# machdongho.net
KiCad netlist of a schematic drawn in Altium Designer
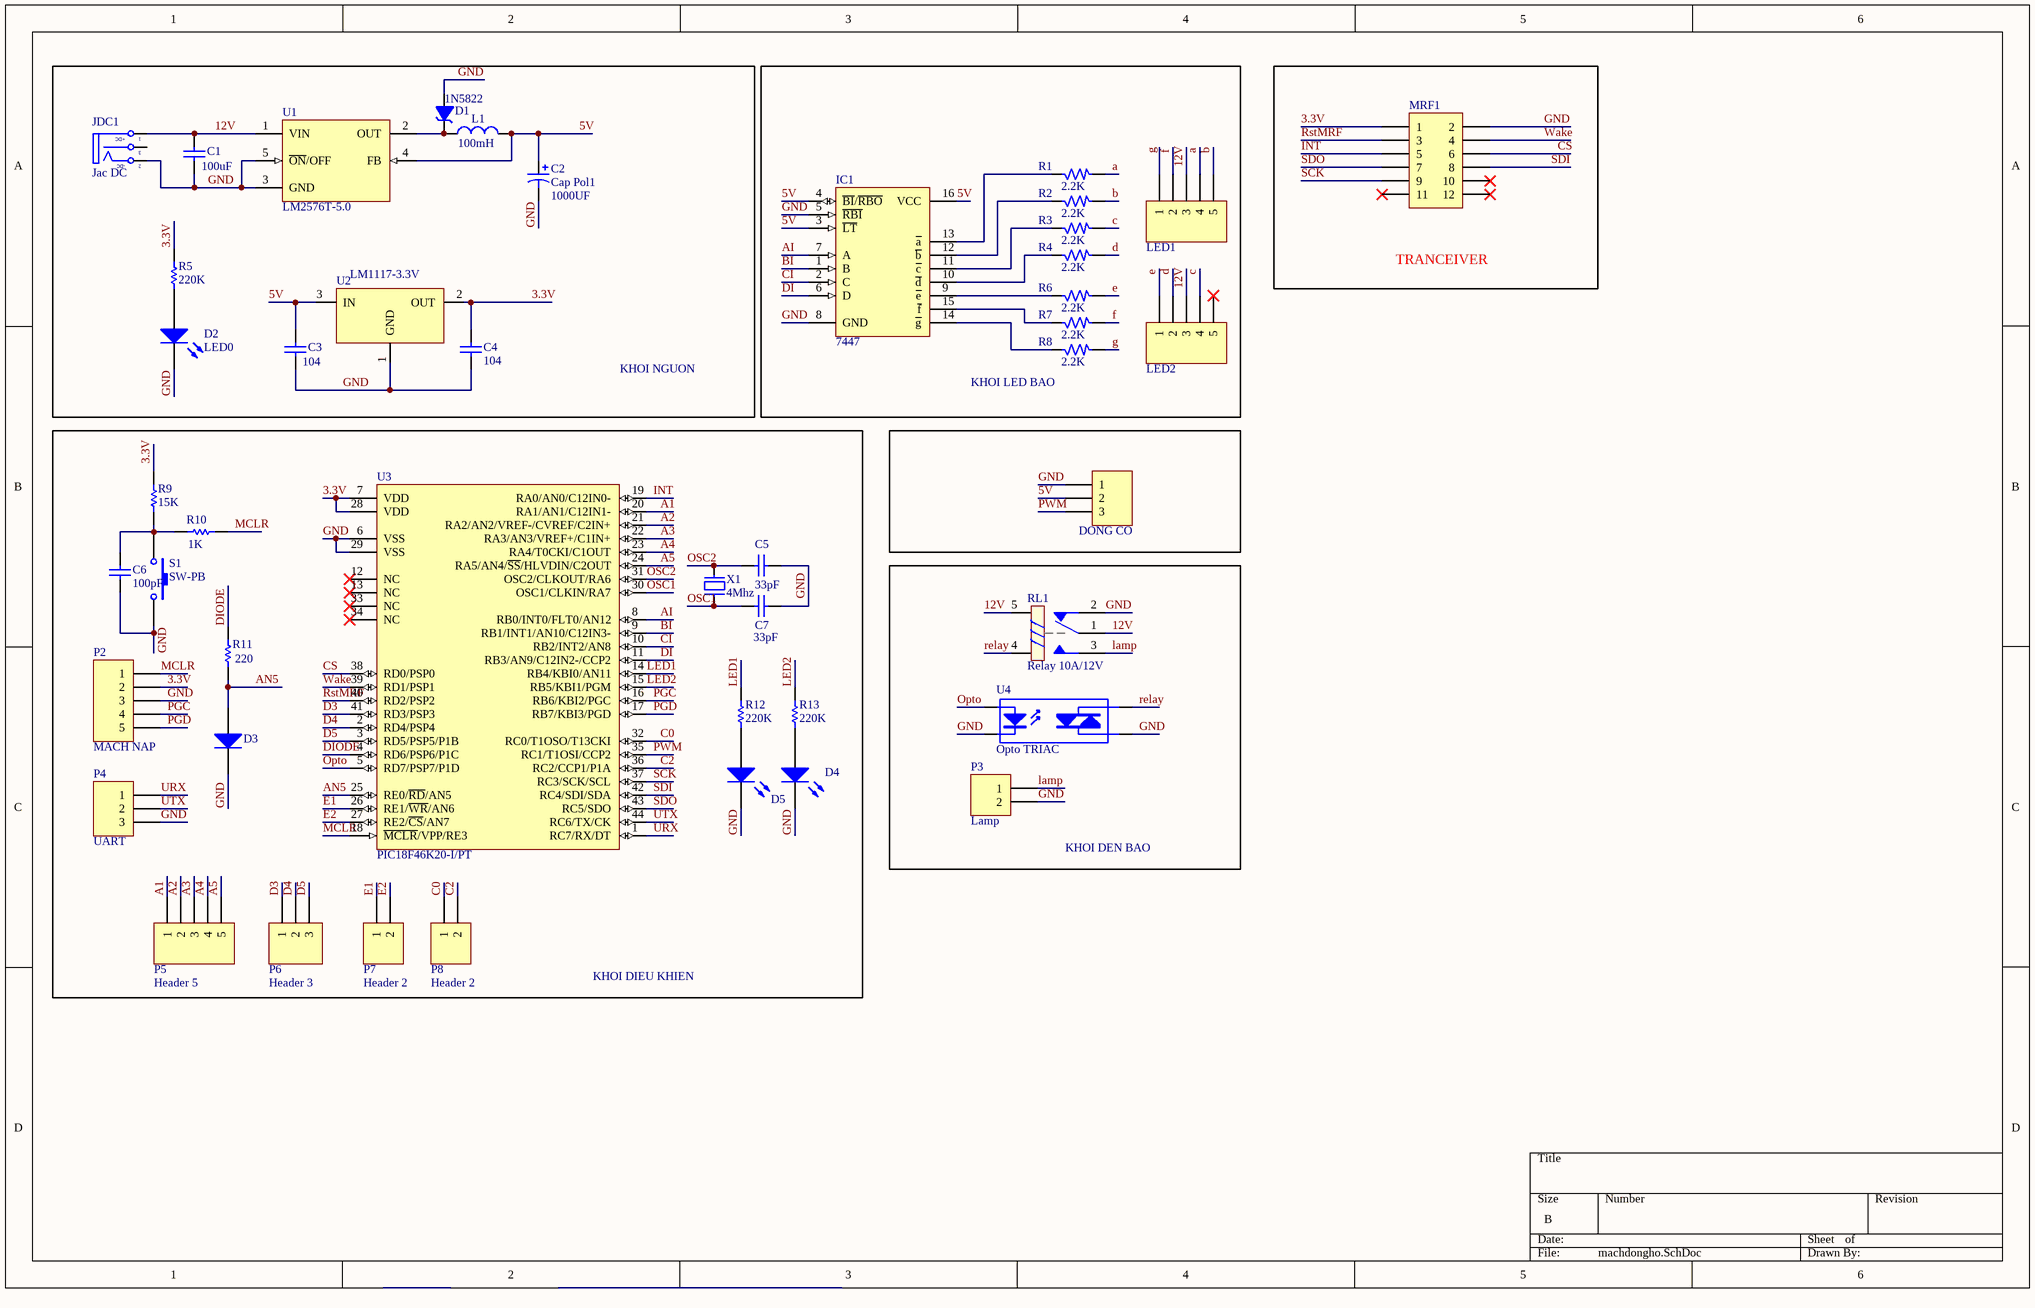
[diagram p0: machdongho.SchDoc]

(export (version "E")
  (design (tool "Eeschema 10.0.6"))
  (components
    (comp (ref "C1")
      (value "100uF")
      (footprint "SMD Capacistor 1206")
      (description "Capacitor")
      (fields (field (name "Comment") "Cap") (field (name "PUBLISHER") "Altium Limited"))
      (libsource (lib "Miscellaneous Devices") (part "Cap"))
    )
    (comp (ref "C2")
      (value "Cap Pol1")
      (footprint "SMD Capacistor 1206")
      (description "Polarized Capacitor (Radial)")
      (fields (field (name "ALTIUM_VALUE") "1000UF") (field (name "PUBLISHER") "Altium Limited"))
      (libsource (lib "Miscellaneous Devices") (part "Cap Pol1"))
    )
    (comp (ref "C3")
      (value "104")
      (footprint "SM-0805")
      (description "Capacitor")
      (fields (field (name "Comment") "Cap") (field (name "PUBLISHER") "Altium Limited"))
      (libsource (lib "Miscellaneous Devices") (part "Cap"))
    )
    (comp (ref "C4")
      (value "104")
      (footprint "SM-0805")
      (description "Capacitor")
      (fields (field (name "Comment") "Cap") (field (name "PUBLISHER") "Altium Limited"))
      (libsource (lib "Miscellaneous Devices") (part "Cap"))
    )
    (comp (ref "C5")
      (value "33pF")
      (footprint "SM-0805")
      (description "Capacitor")
      (fields (field (name "PUBLISHER") "Altium Limited"))
      (libsource (lib "Miscellaneous Devices") (part "Cap"))
    )
    (comp (ref "C6")
      (value "100pF")
      (footprint "SM-0805")
      (description "Capacitor")
      (fields (field (name "Comment") "Cap") (field (name "PUBLISHER") "Altium Limited"))
      (libsource (lib "Miscellaneous Devices") (part "Cap"))
    )
    (comp (ref "C7")
      (value "33pF")
      (footprint "SM-0805")
      (description "Capacitor")
      (fields (field (name "PUBLISHER") "Altium Limited"))
      (libsource (lib "Miscellaneous Devices") (part "Cap"))
    )
    (comp (ref "D1")
      (value "1N5822")
      (footprint "DZ0.5A")
      (description "Diode Zenner")
      (libsource (lib "syhaunguyen") (part "DZ"))
    )
    (comp (ref "D2")
      (value "LED0")
      (footprint "LED-5 GRe")
      (description "Typical INFRARED GaAs LED")
      (fields (field (name "PUBLISHER") "Altium Limited"))
      (libsource (lib "Miscellaneous Devices") (part "LED0"))
    )
    (comp (ref "D3")
      (value "Diode")
      (footprint "SMC")
      (description "Default Diode")
      (fields (field (name "PUBLISHER") "Altium Limited"))
      (libsource (lib "Miscellaneous Devices") (part "Diode"))
    )
    (comp (ref "D4")
      (value "~")
      (footprint "LED-5 GRe")
      (description "Typical INFRARED GaAs LED")
      (fields (field (name "PUBLISHER") "Altium Limited"))
      (libsource (lib "Miscellaneous Devices") (part "LED0"))
    )
    (comp (ref "D5")
      (value "~")
      (footprint "LED-5 GRe")
      (description "Typical INFRARED GaAs LED")
      (fields (field (name "PUBLISHER") "Altium Limited"))
      (libsource (lib "Miscellaneous Devices") (part "LED0"))
    )
    (comp (ref "IC1")
      (value "7447")
      (footprint "DIP16/W0.3")
      (description "VanDungEvn")
      (libsource (lib "syhaunguyen") (part "7447"))
    )
    (comp (ref "JDC1")
      (value "Jac DC")
      (footprint "DC-IN")
      (description "Jac DC input")
      (libsource (lib "syhaunguyen") (part "DCIN"))
    )
    (comp (ref "L1")
      (value "100mH")
      (footprint "L/0.4")
      (description "Inductor")
      (libsource (lib "syhaunguyen") (part "L1"))
    )
    (comp (ref "LED1")
      (value "Led7")
      (footprint "HDR1X5")
      (description "Header, 5-Pin")
      (fields (field (name "PUBLISHER") "Altium Limited"))
      (libsource (lib "Miscellaneous Connectors") (part "Header 5"))
    )
    (comp (ref "LED2")
      (value "Led7")
      (footprint "HDR1X5")
      (description "Header, 5-Pin")
      (fields (field (name "PUBLISHER") "Altium Limited"))
      (libsource (lib "Miscellaneous Connectors") (part "Header 5"))
    )
    (comp (ref "MRF1")
      (value "Header 6X2")
      (footprint "MRF24J40MB_board_mini")
      (description "Header, 6-Pin, Dual row")
      (fields (field (name "PUBLISHER") "Altium Limited"))
      (libsource (lib "Miscellaneous Connectors") (part "Header 6X2"))
    )
    (comp (ref "P1")
      (value "DONG CO")
      (footprint "HDR1X3")
      (description "Header, 3-Pin")
      (fields (field (name "PUBLISHER") "Altium Limited"))
      (libsource (lib "Miscellaneous Connectors") (part "Header 3"))
    )
    (comp (ref "P2")
      (value "MACH NAP")
      (footprint "HDR1X5")
      (description "Header, 5-Pin")
      (fields (field (name "PUBLISHER") "Altium Limited"))
      (libsource (lib "") (part "Header 5_1"))
    )
    (comp (ref "P3")
      (value "Lamp")
      (footprint "HDR1X2")
      (description "Header, 2-Pin")
      (fields (field (name "PUBLISHER") "Altium Limited"))
      (libsource (lib "") (part "Header 2_1"))
    )
    (comp (ref "P4")
      (value "UART")
      (footprint "HDR1X3")
      (description "Header, 3-Pin")
      (fields (field (name "PUBLISHER") "Altium Limited"))
      (libsource (lib "") (part "Header 3_2"))
    )
    (comp (ref "P5")
      (value "Header 5")
      (footprint "HDR1X5")
      (description "Header, 5-Pin")
      (fields (field (name "PUBLISHER") "Altium Limited"))
      (libsource (lib "Miscellaneous Connectors") (part "Header 5"))
    )
    (comp (ref "P6")
      (value "Header 3")
      (footprint "HDR1X3")
      (description "Header, 3-Pin")
      (fields (field (name "PUBLISHER") "Altium Limited"))
      (libsource (lib "") (part "Header 3_1"))
    )
    (comp (ref "P7")
      (value "Header 2")
      (footprint "HDR1X2")
      (description "Header, 2-Pin")
      (fields (field (name "PUBLISHER") "Altium Limited"))
      (libsource (lib "Miscellaneous Connectors") (part "Header 2"))
    )
    (comp (ref "P8")
      (value "Header 2")
      (footprint "HDR1X2")
      (description "Header, 2-Pin")
      (fields (field (name "PUBLISHER") "Altium Limited"))
      (libsource (lib "Miscellaneous Connectors") (part "Header 2"))
    )
    (comp (ref "R1")
      (value "2.2K")
      (footprint "SM-0805")
      (description "Resistor 1/4W")
      (libsource (lib "syhaunguyen") (part "R"))
    )
    (comp (ref "R2")
      (value "2.2K")
      (footprint "SM-0805")
      (description "Resistor 1/4W")
      (libsource (lib "syhaunguyen") (part "R"))
    )
    (comp (ref "R3")
      (value "2.2K")
      (footprint "SM-0805")
      (description "Resistor 1/4W")
      (libsource (lib "syhaunguyen") (part "R"))
    )
    (comp (ref "R4")
      (value "2.2K")
      (footprint "SM-0805")
      (description "Resistor 1/4W")
      (libsource (lib "syhaunguyen") (part "R"))
    )
    (comp (ref "R5")
      (value "220K")
      (footprint "SM-0805")
      (description "Resistor")
      (fields (field (name "Comment") "Res1") (field (name "PUBLISHER") "Altium Limited"))
      (libsource (lib "Miscellaneous Devices") (part "Res1"))
    )
    (comp (ref "R6")
      (value "2.2K")
      (footprint "SM-0805")
      (description "Resistor 1/4W")
      (libsource (lib "syhaunguyen") (part "R"))
    )
    (comp (ref "R7")
      (value "2.2K")
      (footprint "SM-0805")
      (description "Resistor 1/4W")
      (libsource (lib "syhaunguyen") (part "R"))
    )
    (comp (ref "R8")
      (value "2.2K")
      (footprint "SM-0805")
      (description "Resistor 1/4W")
      (libsource (lib "syhaunguyen") (part "R"))
    )
    (comp (ref "R9")
      (value "15K")
      (footprint "SM-0805")
      (description "Resistor")
      (fields (field (name "PUBLISHER") "Altium Limited"))
      (libsource (lib "Miscellaneous Devices") (part "Res1"))
    )
    (comp (ref "R10")
      (value "1K")
      (footprint "SM-0805")
      (description "Semiconductor Resistor")
      (fields (field (name "Comment") "Res Semi") (field (name "PUBLISHER") "Altium Limited"))
      (libsource (lib "Miscellaneous Devices") (part "Res Semi"))
    )
    (comp (ref "R11")
      (value "220")
      (footprint "SM-0805")
      (description "Resistor")
      (fields (field (name "Comment") "Res1") (field (name "PUBLISHER") "Altium Limited"))
      (libsource (lib "Miscellaneous Devices") (part "Res1"))
    )
    (comp (ref "R12")
      (value "220K")
      (footprint "SM-0805")
      (description "Resistor")
      (fields (field (name "Comment") "Res1") (field (name "PUBLISHER") "Altium Limited"))
      (libsource (lib "Miscellaneous Devices") (part "Res1"))
    )
    (comp (ref "R13")
      (value "220K")
      (footprint "SM-0805")
      (description "Resistor")
      (fields (field (name "Comment") "Res1") (field (name "PUBLISHER") "Altium Limited"))
      (libsource (lib "Miscellaneous Devices") (part "Res1"))
    )
    (comp (ref "RL1")
      (value "Relay 10A/12V")
      (footprint "RL_SPDT_10A")
      (description "Relay SPDT,10A - 12VDC 5 Pin")
      (libsource (lib "syhaunguyen") (part "Relay 1"))
    )
    (comp (ref "S1")
      (value "SW-PB")
      (footprint "SW2")
      (description "Switch")
      (fields (field (name "PUBLISHER") "Altium Limited"))
      (libsource (lib "Miscellaneous Devices") (part "SW-PB"))
    )
    (comp (ref "U1")
      (value "LM2576T-5.0")
      (footprint "LM2576t")
      (description "SIMPLE SWITCHER; 3A Step-Down Voltage Regulator")
      (fields
        (field (name "MANUFACTURER") "National Semiconductor")
        (field (name "DIGIKEYPARTNUMBER") "LM2576T-5.0-ND")
        (field (name "PUBLISHER") "Altium Limited")
      )
      (libsource (lib "General IC") (part "LM2576T-5.0"))
    )
    (comp (ref "U2")
      (value "LM1117-3.3V")
      (footprint "LM1117-SOP")
      (description "800mA Low-Dropout Linear Regulator")
      (fields (field (name "CREATOR") "Nguyen Ba Bien"))
      (libsource (lib "General IC") (part "LM1117"))
    )
    (comp (ref "U3")
      (value "PIC18F46K20-I/PT")
      (footprint "TQFP-PT44_N")
      (fields (field (name "PUBLISHER") "Altium Limited"))
      (libsource (lib "Microchip Microcontroller 8-Bit PIC18") (part "PIC18F46K20-I/PT"))
    )
    (comp (ref "U4")
      (value "Opto TRIAC")
      (footprint "DIP4/W0.3")
      (description "Opto-Triac")
      (fields (field (name "PUBLISHER") "Altium Limited"))
      (libsource (lib "Miscellaneous Devices") (part "Opto TRIAC"))
    )
    (comp (ref "X1")
      (value "4Mhz")
      (footprint "XT2")
      (description "Crystal For all Crystal 2pin.")
      (libsource (lib "syhaunguyen") (part "XT2"))
    )
  )
  (nets
    (net (code "1") (name "/3.3V") (class "Default")
      (node (ref "C4") (pin "2") (pinfunction "2_2") (pintype "passive"))
      (node (ref "MRF1") (pin "1") (pinfunction "1_1") (pintype "passive"))
      (node (ref "P2") (pin "2") (pinfunction "2_2") (pintype "passive"))
      (node (ref "R5") (pin "1") (pinfunction "1_1") (pintype "passive"))
      (node (ref "R9") (pin "2") (pinfunction "2_2") (pintype "passive"))
      (node (ref "U2") (pin "2") (pinfunction "OUT_2") (pintype "passive"))
      (node (ref "U3") (pin "28") (pinfunction "VDD_28") (pintype "power_in"))
      (node (ref "U3") (pin "7") (pinfunction "VDD_7") (pintype "power_in"))
    )
    (net (code "2") (name "/5V") (class "Default")
      (node (ref "C2") (pin "1") (pinfunction "1_1") (pintype "passive"))
      (node (ref "C3") (pin "2") (pinfunction "2_2") (pintype "passive"))
      (node (ref "IC1") (pin "16") (pinfunction "VCC_16") (pintype "power_in"))
      (node (ref "IC1") (pin "3") (pinfunction "~{LT}_3") (pintype "input"))
      (node (ref "IC1") (pin "4") (pinfunction "~{BI}/~{RBO}_4") (pintype "bidirectional"))
      (node (ref "L1") (pin "2") (pinfunction "2_2") (pintype "passive"))
      (node (ref "P1") (pin "2") (pinfunction "2_2") (pintype "passive"))
      (node (ref "U1") (pin "4") (pinfunction "FB_4") (pintype "input"))
      (node (ref "U2") (pin "3") (pinfunction "IN_3") (pintype "passive"))
    )
    (net (code "3") (name "/12V") (class "Default")
      (node (ref "C1") (pin "2") (pinfunction "2_2") (pintype "passive"))
      (node (ref "JDC1") (pin "1") (pinfunction "T_1") (pintype "passive"))
      (node (ref "LED1") (pin "3") (pinfunction "3_3") (pintype "passive"))
      (node (ref "LED2") (pin "3") (pinfunction "3_3") (pintype "passive"))
      (node (ref "RL1") (pin "1") (pinfunction "1_1") (pintype "passive"))
      (node (ref "RL1") (pin "5") (pinfunction "5_5") (pintype "passive"))
      (node (ref "U1") (pin "1") (pinfunction "VIN_1") (pintype "power_in"))
    )
    (net (code "4") (name "/A1") (class "Default")
      (node (ref "P5") (pin "1") (pinfunction "1_1") (pintype "passive"))
      (node (ref "U3") (pin "20") (pinfunction "RA1/AN1/C12IN1-_20") (pintype "bidirectional"))
    )
    (net (code "5") (name "/A2") (class "Default")
      (node (ref "P5") (pin "2") (pinfunction "2_2") (pintype "passive"))
      (node (ref "U3") (pin "21") (pinfunction "RA2/AN2/VREF-/CVREF/C2IN+_21") (pintype "bidirectional"))
    )
    (net (code "6") (name "/A3") (class "Default")
      (node (ref "P5") (pin "3") (pinfunction "3_3") (pintype "passive"))
      (node (ref "U3") (pin "22") (pinfunction "RA3/AN3/VREF+/C1IN+_22") (pintype "bidirectional"))
    )
    (net (code "7") (name "/A4") (class "Default")
      (node (ref "P5") (pin "4") (pinfunction "4_4") (pintype "passive"))
      (node (ref "U3") (pin "23") (pinfunction "RA4/T0CKI/C1OUT_23") (pintype "bidirectional"))
    )
    (net (code "8") (name "/A5") (class "Default")
      (node (ref "P5") (pin "5") (pinfunction "5_5") (pintype "passive"))
      (node (ref "U3") (pin "24") (pinfunction "RA5/AN4/~{SS}/HLVDIN/C2OUT_24") (pintype "bidirectional"))
    )
    (net (code "9") (name "/AI") (class "Default")
      (node (ref "IC1") (pin "7") (pinfunction "A_7") (pintype "input"))
      (node (ref "U3") (pin "8") (pinfunction "RB0/INT0/FLT0/AN12_8") (pintype "bidirectional"))
    )
    (net (code "10") (name "/AN5") (class "Default")
      (node (ref "D3") (pin "1") (pinfunction "A_1") (pintype "passive"))
      (node (ref "R11") (pin "1") (pinfunction "1_1") (pintype "passive"))
      (node (ref "U3") (pin "25") (pinfunction "RE0/~{RD}/AN5_25") (pintype "bidirectional"))
    )
    (net (code "11") (name "/BI") (class "Default")
      (node (ref "IC1") (pin "1") (pinfunction "B_1") (pintype "input"))
      (node (ref "U3") (pin "9") (pinfunction "RB1/INT1/AN10/C12IN3-_9") (pintype "bidirectional"))
    )
    (net (code "12") (name "/C0") (class "Default")
      (node (ref "P8") (pin "1") (pinfunction "1_1") (pintype "passive"))
      (node (ref "U3") (pin "32") (pinfunction "RC0/T1OSO/T13CKI_32") (pintype "bidirectional"))
    )
    (net (code "13") (name "/C2") (class "Default")
      (node (ref "P8") (pin "2") (pinfunction "2_2") (pintype "passive"))
      (node (ref "U3") (pin "36") (pinfunction "RC2/CCP1/P1A_36") (pintype "bidirectional"))
    )
    (net (code "14") (name "/CI") (class "Default")
      (node (ref "IC1") (pin "2") (pinfunction "C_2") (pintype "input"))
      (node (ref "U3") (pin "10") (pinfunction "RB2/INT2/AN8_10") (pintype "bidirectional"))
    )
    (net (code "15") (name "/CS") (class "Default")
      (node (ref "MRF1") (pin "6") (pinfunction "6_6") (pintype "passive"))
      (node (ref "U3") (pin "38") (pinfunction "RD0/PSP0_38") (pintype "bidirectional"))
    )
    (net (code "16") (name "/D3") (class "Default")
      (node (ref "P6") (pin "1") (pinfunction "1_1") (pintype "passive"))
      (node (ref "U3") (pin "41") (pinfunction "RD3/PSP3_41") (pintype "bidirectional"))
    )
    (net (code "17") (name "/D4") (class "Default")
      (node (ref "P6") (pin "2") (pinfunction "2_2") (pintype "passive"))
      (node (ref "U3") (pin "2") (pinfunction "RD4/PSP4_2") (pintype "bidirectional"))
    )
    (net (code "18") (name "/D5") (class "Default")
      (node (ref "P6") (pin "3") (pinfunction "3_3") (pintype "passive"))
      (node (ref "U3") (pin "3") (pinfunction "RD5/PSP5/P1B_3") (pintype "bidirectional"))
    )
    (net (code "19") (name "/DI") (class "Default")
      (node (ref "IC1") (pin "6") (pinfunction "D_6") (pintype "input"))
      (node (ref "U3") (pin "11") (pinfunction "RB3/AN9/C12IN2-/CCP2_11") (pintype "bidirectional"))
    )
    (net (code "20") (name "/DIODE") (class "Default")
      (node (ref "R11") (pin "2") (pinfunction "2_2") (pintype "passive"))
      (node (ref "U3") (pin "4") (pinfunction "RD6/PSP6/P1C_4") (pintype "bidirectional"))
    )
    (net (code "21") (name "/E1") (class "Default")
      (node (ref "P7") (pin "1") (pinfunction "1_1") (pintype "passive"))
      (node (ref "U3") (pin "26") (pinfunction "RE1/~{WR}/AN6_26") (pintype "bidirectional"))
    )
    (net (code "22") (name "/E2") (class "Default")
      (node (ref "P7") (pin "2") (pinfunction "2_2") (pintype "passive"))
      (node (ref "U3") (pin "27") (pinfunction "RE2/~{CS}/AN7_27") (pintype "bidirectional"))
    )
    (net (code "23") (name "/GND") (class "Default")
      (node (ref "C1") (pin "1") (pinfunction "1_1") (pintype "passive"))
      (node (ref "C2") (pin "2") (pinfunction "2_2") (pintype "passive"))
      (node (ref "C3") (pin "1") (pinfunction "1_1") (pintype "passive"))
      (node (ref "C4") (pin "1") (pinfunction "1_1") (pintype "passive"))
      (node (ref "C5") (pin "1") (pinfunction "1_1") (pintype "passive"))
      (node (ref "C6") (pin "2") (pinfunction "2_2") (pintype "passive"))
      (node (ref "C7") (pin "1") (pinfunction "1_1") (pintype "passive"))
      (node (ref "D1") (pin "1") (pinfunction "A_1") (pintype "passive"))
      (node (ref "D2") (pin "2") (pinfunction "K_2") (pintype "passive"))
      (node (ref "D3") (pin "2") (pinfunction "K_2") (pintype "passive"))
      (node (ref "D4") (pin "2") (pinfunction "K_2") (pintype "passive"))
      (node (ref "D5") (pin "2") (pinfunction "K_2") (pintype "passive"))
      (node (ref "IC1") (pin "5") (pinfunction "~{RBI}_5") (pintype "input"))
      (node (ref "IC1") (pin "8") (pinfunction "GND_8") (pintype "power_in"))
      (node (ref "JDC1") (pin "2") (pinfunction "TN_2") (pintype "passive"))
      (node (ref "MRF1") (pin "2") (pinfunction "2_2") (pintype "passive"))
      (node (ref "P1") (pin "1") (pinfunction "1_1") (pintype "passive"))
      (node (ref "P2") (pin "3") (pinfunction "3_3") (pintype "passive"))
      (node (ref "P3") (pin "2") (pinfunction "2_2") (pintype "passive"))
      (node (ref "P4") (pin "3") (pinfunction "3_3") (pintype "passive"))
      (node (ref "RL1") (pin "2") (pinfunction "2_2") (pintype "passive"))
      (node (ref "S1") (pin "2") (pinfunction "2_2") (pintype "passive"))
      (node (ref "U1") (pin "3") (pinfunction "GND_3") (pintype "power_in"))
      (node (ref "U1") (pin "5") (pinfunction "~{ON}/OFF_5") (pintype "input"))
      (node (ref "U2") (pin "1") (pinfunction "GND_1") (pintype "passive"))
      (node (ref "U3") (pin "29") (pinfunction "VSS_29") (pintype "power_in"))
      (node (ref "U3") (pin "6") (pinfunction "VSS_6") (pintype "power_in"))
      (node (ref "U4") (pin "2") (pinfunction "K_2") (pintype "passive"))
      (node (ref "U4") (pin "4") (pinfunction "A/K_4") (pintype "passive"))
    )
    (net (code "24") (name "/INT") (class "Default")
      (node (ref "MRF1") (pin "5") (pinfunction "5_5") (pintype "passive"))
      (node (ref "U3") (pin "19") (pinfunction "RA0/AN0/C12IN0-_19") (pintype "bidirectional"))
    )
    (net (code "25") (name "/LED1") (class "Default")
      (node (ref "R12") (pin "1") (pinfunction "1_1") (pintype "passive"))
      (node (ref "U3") (pin "14") (pinfunction "RB4/KBI0/AN11_14") (pintype "bidirectional"))
    )
    (net (code "26") (name "/LED2") (class "Default")
      (node (ref "R13") (pin "1") (pinfunction "1_1") (pintype "passive"))
      (node (ref "U3") (pin "15") (pinfunction "RB5/KBI1/PGM_15") (pintype "bidirectional"))
    )
    (net (code "27") (name "/MCLR") (class "Default")
      (node (ref "P2") (pin "1") (pinfunction "1_1") (pintype "passive"))
      (node (ref "R10") (pin "2") (pinfunction "2_2") (pintype "passive"))
      (node (ref "U3") (pin "18") (pinfunction "~{MCLR}/VPP/RE3_18") (pintype "input"))
    )
    (net (code "28") (name "/OSC1") (class "Default")
      (node (ref "C7") (pin "2") (pinfunction "2_2") (pintype "passive"))
      (node (ref "U3") (pin "30") (pinfunction "OSC1/CLKIN/RA7_30") (pintype "bidirectional"))
      (node (ref "X1") (pin "1") (pinfunction "1_1") (pintype "passive"))
    )
    (net (code "29") (name "/OSC2") (class "Default")
      (node (ref "C5") (pin "2") (pinfunction "2_2") (pintype "passive"))
      (node (ref "U3") (pin "31") (pinfunction "OSC2/CLKOUT/RA6_31") (pintype "bidirectional"))
      (node (ref "X1") (pin "2") (pinfunction "2_2") (pintype "passive"))
    )
    (net (code "30") (name "/Opto") (class "Default")
      (node (ref "U3") (pin "5") (pinfunction "RD7/PSP7/P1D_5") (pintype "bidirectional"))
      (node (ref "U4") (pin "1") (pinfunction "A_1") (pintype "passive"))
    )
    (net (code "31") (name "/PGC") (class "Default")
      (node (ref "P2") (pin "4") (pinfunction "4_4") (pintype "passive"))
      (node (ref "U3") (pin "16") (pinfunction "RB6/KBI2/PGC_16") (pintype "bidirectional"))
    )
    (net (code "32") (name "/PGD") (class "Default")
      (node (ref "P2") (pin "5") (pinfunction "5_5") (pintype "passive"))
      (node (ref "U3") (pin "17") (pinfunction "RB7/KBI3/PGD_17") (pintype "bidirectional"))
    )
    (net (code "33") (name "/PWM") (class "Default")
      (node (ref "P1") (pin "3") (pinfunction "3_3") (pintype "passive"))
      (node (ref "U3") (pin "35") (pinfunction "RC1/T1OSI/CCP2_35") (pintype "bidirectional"))
    )
    (net (code "34") (name "/RstMRF") (class "Default")
      (node (ref "MRF1") (pin "3") (pinfunction "3_3") (pintype "passive"))
      (node (ref "U3") (pin "40") (pinfunction "RD2/PSP2_40") (pintype "bidirectional"))
    )
    (net (code "35") (name "/SCK") (class "Default")
      (node (ref "MRF1") (pin "9") (pinfunction "9_9") (pintype "passive"))
      (node (ref "U3") (pin "37") (pinfunction "RC3/SCK/SCL_37") (pintype "bidirectional"))
    )
    (net (code "36") (name "/SDI") (class "Default")
      (node (ref "MRF1") (pin "8") (pinfunction "8_8") (pintype "passive"))
      (node (ref "U3") (pin "42") (pinfunction "RC4/SDI/SDA_42") (pintype "bidirectional"))
    )
    (net (code "37") (name "/SDO") (class "Default")
      (node (ref "MRF1") (pin "7") (pinfunction "7_7") (pintype "passive"))
      (node (ref "U3") (pin "43") (pinfunction "RC5/SDO_43") (pintype "bidirectional"))
    )
    (net (code "38") (name "/URX") (class "Default")
      (node (ref "P4") (pin "1") (pinfunction "1_1") (pintype "passive"))
      (node (ref "U3") (pin "1") (pinfunction "RC7/RX/DT_1") (pintype "bidirectional"))
    )
    (net (code "39") (name "/UTX") (class "Default")
      (node (ref "P4") (pin "2") (pinfunction "2_2") (pintype "passive"))
      (node (ref "U3") (pin "44") (pinfunction "RC6/TX/CK_44") (pintype "bidirectional"))
    )
    (net (code "40") (name "/Wake") (class "Default")
      (node (ref "MRF1") (pin "4") (pinfunction "4_4") (pintype "passive"))
      (node (ref "U3") (pin "39") (pinfunction "RD1/PSP1_39") (pintype "bidirectional"))
    )
    (net (code "41") (name "/a") (class "Default")
      (node (ref "LED1") (pin "4") (pinfunction "4_4") (pintype "passive"))
      (node (ref "R1") (pin "2") (pinfunction "2_2") (pintype "passive"))
    )
    (net (code "42") (name "/b") (class "Default")
      (node (ref "LED1") (pin "5") (pinfunction "5_5") (pintype "passive"))
      (node (ref "R2") (pin "2") (pinfunction "2_2") (pintype "passive"))
    )
    (net (code "43") (name "/c") (class "Default")
      (node (ref "LED2") (pin "4") (pinfunction "4_4") (pintype "passive"))
      (node (ref "R3") (pin "2") (pinfunction "2_2") (pintype "passive"))
    )
    (net (code "44") (name "/d") (class "Default")
      (node (ref "LED2") (pin "2") (pinfunction "2_2") (pintype "passive"))
      (node (ref "R4") (pin "2") (pinfunction "2_2") (pintype "passive"))
    )
    (net (code "45") (name "/e") (class "Default")
      (node (ref "LED2") (pin "1") (pinfunction "1_1") (pintype "passive"))
      (node (ref "R6") (pin "2") (pinfunction "2_2") (pintype "passive"))
    )
    (net (code "46") (name "/f") (class "Default")
      (node (ref "LED1") (pin "2") (pinfunction "2_2") (pintype "passive"))
      (node (ref "R7") (pin "2") (pinfunction "2_2") (pintype "passive"))
    )
    (net (code "47") (name "/g") (class "Default")
      (node (ref "LED1") (pin "1") (pinfunction "1_1") (pintype "passive"))
      (node (ref "R8") (pin "2") (pinfunction "2_2") (pintype "passive"))
    )
    (net (code "48") (name "/lamp") (class "Default")
      (node (ref "P3") (pin "1") (pinfunction "1_1") (pintype "passive"))
      (node (ref "RL1") (pin "3") (pinfunction "3_3") (pintype "passive"))
    )
    (net (code "49") (name "/relay") (class "Default")
      (node (ref "RL1") (pin "4") (pinfunction "4_4") (pintype "passive"))
      (node (ref "U4") (pin "3") (pinfunction "A/K_3") (pintype "passive"))
    )
    (net (code "50") (name "Net-(C6-Pad1)") (class "Default")
      (node (ref "C6") (pin "1") (pinfunction "1_1") (pintype "passive"))
      (node (ref "R10") (pin "1") (pinfunction "1_1") (pintype "passive"))
      (node (ref "R9") (pin "1") (pinfunction "1_1") (pintype "passive"))
      (node (ref "S1") (pin "1") (pinfunction "1_1") (pintype "passive"))
    )
    (net (code "51") (name "Net-(D1-K)") (class "Default")
      (node (ref "D1") (pin "2") (pinfunction "K_2") (pintype "passive"))
      (node (ref "L1") (pin "1") (pinfunction "1_1") (pintype "passive"))
      (node (ref "U1") (pin "2") (pinfunction "OUT_2") (pintype "power_in"))
    )
    (net (code "52") (name "Net-(D2-A)") (class "Default")
      (node (ref "D2") (pin "1") (pinfunction "A_1") (pintype "passive"))
      (node (ref "R5") (pin "2") (pinfunction "2_2") (pintype "passive"))
    )
    (net (code "53") (name "Net-(D4-A)") (class "Default")
      (node (ref "D4") (pin "1") (pinfunction "A_1") (pintype "passive"))
      (node (ref "R13") (pin "2") (pinfunction "2_2") (pintype "passive"))
    )
    (net (code "54") (name "Net-(D5-A)") (class "Default")
      (node (ref "D5") (pin "1") (pinfunction "A_1") (pintype "passive"))
      (node (ref "R12") (pin "2") (pinfunction "2_2") (pintype "passive"))
    )
    (net (code "55") (name "Net-(IC1-~{a})") (class "Default")
      (node (ref "IC1") (pin "13") (pinfunction "~{a}_13") (pintype "open_collector"))
      (node (ref "R1") (pin "1") (pinfunction "1_1") (pintype "passive"))
    )
    (net (code "56") (name "Net-(IC1-~{b})") (class "Default")
      (node (ref "IC1") (pin "12") (pinfunction "~{b}_12") (pintype "open_collector"))
      (node (ref "R2") (pin "1") (pinfunction "1_1") (pintype "passive"))
    )
    (net (code "57") (name "Net-(IC1-~{c})") (class "Default")
      (node (ref "IC1") (pin "11") (pinfunction "~{c}_11") (pintype "open_collector"))
      (node (ref "R3") (pin "1") (pinfunction "1_1") (pintype "passive"))
    )
    (net (code "58") (name "Net-(IC1-~{d})") (class "Default")
      (node (ref "IC1") (pin "10") (pinfunction "~{d}_10") (pintype "open_collector"))
      (node (ref "R4") (pin "1") (pinfunction "1_1") (pintype "passive"))
    )
    (net (code "59") (name "Net-(IC1-~{e})") (class "Default")
      (node (ref "IC1") (pin "9") (pinfunction "~{e}_9") (pintype "open_collector"))
      (node (ref "R6") (pin "1") (pinfunction "1_1") (pintype "passive"))
    )
    (net (code "60") (name "Net-(IC1-~{f})") (class "Default")
      (node (ref "IC1") (pin "15") (pinfunction "~{f}_15") (pintype "open_collector"))
      (node (ref "R7") (pin "1") (pinfunction "1_1") (pintype "passive"))
    )
    (net (code "61") (name "Net-(IC1-~{g})") (class "Default")
      (node (ref "IC1") (pin "14") (pinfunction "~{g}_14") (pintype "open_collector"))
      (node (ref "R8") (pin "1") (pinfunction "1_1") (pintype "passive"))
    )
    (net (code "62") (name "unconnected-(JDC1-S-Pad3)") (class "Default")
      (node (ref "JDC1") (pin "3") (pinfunction "S_3") (pintype "power_in"))
    )
    (net (code "63") (name "unconnected-(LED2-Pad5)") (class "Default")
      (node (ref "LED2") (pin "5") (pinfunction "5_5") (pintype "passive+no_connect"))
    )
    (net (code "64") (name "unconnected-(MRF1-Pad10)") (class "Default")
      (node (ref "MRF1") (pin "10") (pinfunction "10_10") (pintype "passive+no_connect"))
    )
    (net (code "65") (name "unconnected-(MRF1-Pad11)") (class "Default")
      (node (ref "MRF1") (pin "11") (pinfunction "11_11") (pintype "passive+no_connect"))
    )
    (net (code "66") (name "unconnected-(MRF1-Pad12)") (class "Default")
      (node (ref "MRF1") (pin "12") (pinfunction "12_12") (pintype "passive+no_connect"))
    )
    (net (code "67") (name "unconnected-(U3-NC-Pad12)") (class "Default")
      (node (ref "U3") (pin "12") (pinfunction "NC_12") (pintype "passive+no_connect"))
    )
    (net (code "68") (name "unconnected-(U3-NC-Pad13)") (class "Default")
      (node (ref "U3") (pin "13") (pinfunction "NC_13") (pintype "passive+no_connect"))
    )
    (net (code "69") (name "unconnected-(U3-NC-Pad33)") (class "Default")
      (node (ref "U3") (pin "33") (pinfunction "NC_33") (pintype "passive+no_connect"))
    )
    (net (code "70") (name "unconnected-(U3-NC-Pad34)") (class "Default")
      (node (ref "U3") (pin "34") (pinfunction "NC_34") (pintype "passive+no_connect"))
    )
  )
)
